# CUBO4X4X4.net
KiCad netlist of a schematic drawn in EAGLE
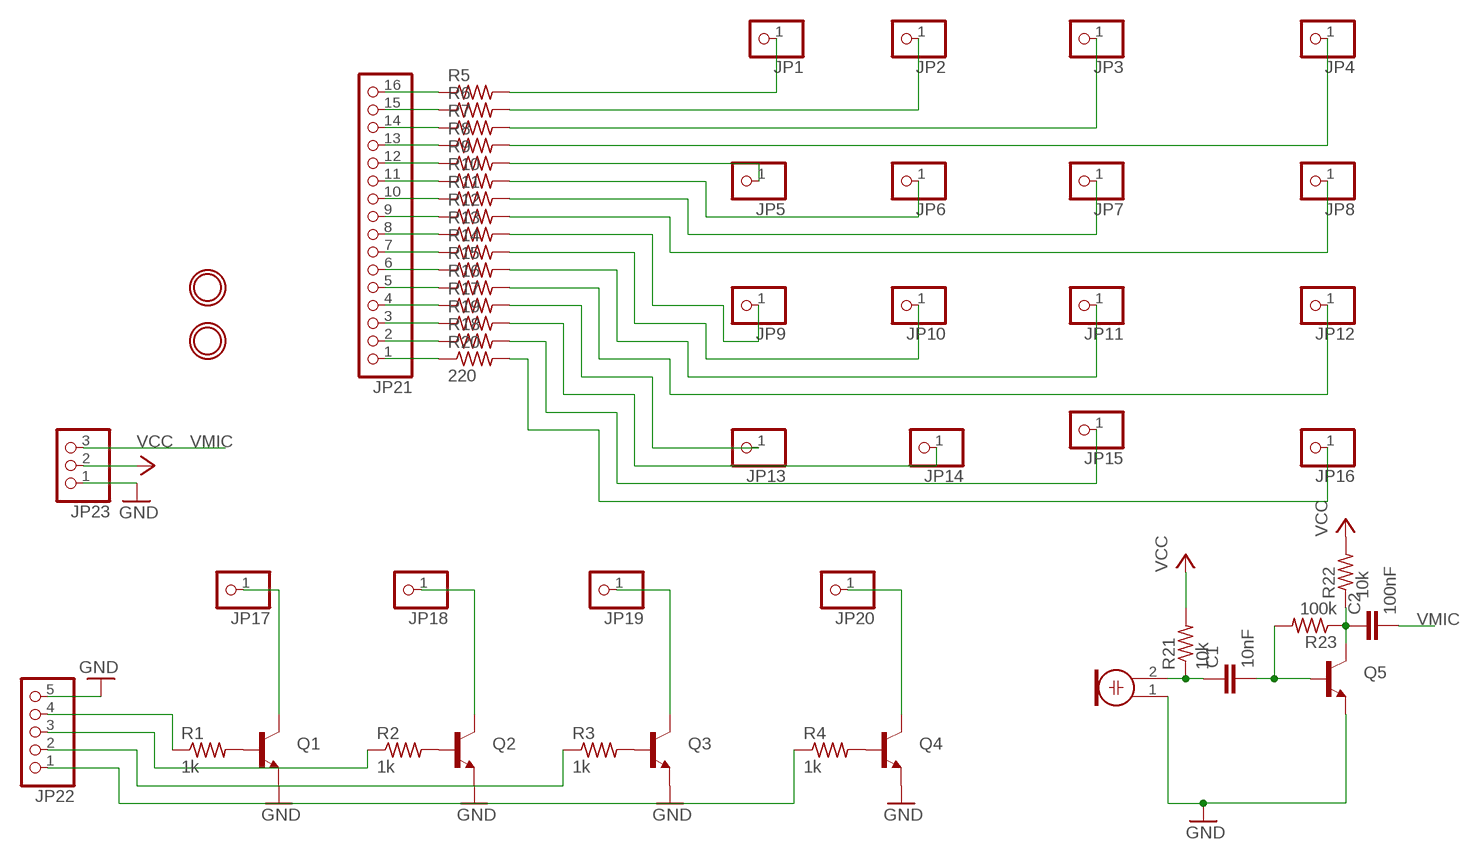
[diagram p0: schematic, sheet 1]

(export (version "E")
  (design (tool "Eeschema 10.0.6"))
  (components
    (comp (ref "C1")
      (value "10nF")
      (footprint "eagle-import:C2.5-2")
      (libsource (lib "eagle-import") (part "C2.5/2"))
    )
    (comp (ref "C2")
      (value "100nF")
      (footprint "eagle-import:C2.5-2")
      (libsource (lib "eagle-import") (part "C2.5/2"))
    )
    (comp (ref "JP1")
      (value "PINHD-1X1")
      (footprint "eagle-import:1X01")
      (libsource (lib "eagle-import") (part "PINHD-1X1"))
    )
    (comp (ref "JP2")
      (value "PINHD-1X1")
      (footprint "eagle-import:1X01")
      (libsource (lib "eagle-import") (part "PINHD-1X1"))
    )
    (comp (ref "JP3")
      (value "PINHD-1X1")
      (footprint "eagle-import:1X01")
      (libsource (lib "eagle-import") (part "PINHD-1X1"))
    )
    (comp (ref "JP4")
      (value "PINHD-1X1")
      (footprint "eagle-import:1X01")
      (libsource (lib "eagle-import") (part "PINHD-1X1"))
    )
    (comp (ref "JP5")
      (value "PINHD-1X1")
      (footprint "eagle-import:1X01")
      (libsource (lib "eagle-import") (part "PINHD-1X1"))
    )
    (comp (ref "JP6")
      (value "PINHD-1X1")
      (footprint "eagle-import:1X01")
      (libsource (lib "eagle-import") (part "PINHD-1X1"))
    )
    (comp (ref "JP7")
      (value "PINHD-1X1")
      (footprint "eagle-import:1X01")
      (libsource (lib "eagle-import") (part "PINHD-1X1"))
    )
    (comp (ref "JP8")
      (value "PINHD-1X1")
      (footprint "eagle-import:1X01")
      (libsource (lib "eagle-import") (part "PINHD-1X1"))
    )
    (comp (ref "JP9")
      (value "PINHD-1X1")
      (footprint "eagle-import:1X01")
      (libsource (lib "eagle-import") (part "PINHD-1X1"))
    )
    (comp (ref "JP10")
      (value "PINHD-1X1")
      (footprint "eagle-import:1X01")
      (libsource (lib "eagle-import") (part "PINHD-1X1"))
    )
    (comp (ref "JP11")
      (value "PINHD-1X1")
      (footprint "eagle-import:1X01")
      (libsource (lib "eagle-import") (part "PINHD-1X1"))
    )
    (comp (ref "JP12")
      (value "PINHD-1X1")
      (footprint "eagle-import:1X01")
      (libsource (lib "eagle-import") (part "PINHD-1X1"))
    )
    (comp (ref "JP13")
      (value "PINHD-1X1")
      (footprint "eagle-import:1X01")
      (libsource (lib "eagle-import") (part "PINHD-1X1"))
    )
    (comp (ref "JP14")
      (value "PINHD-1X1")
      (footprint "eagle-import:1X01")
      (libsource (lib "eagle-import") (part "PINHD-1X1"))
    )
    (comp (ref "JP15")
      (value "PINHD-1X1")
      (footprint "eagle-import:1X01")
      (libsource (lib "eagle-import") (part "PINHD-1X1"))
    )
    (comp (ref "JP16")
      (value "PINHD-1X1")
      (footprint "eagle-import:1X01")
      (libsource (lib "eagle-import") (part "PINHD-1X1"))
    )
    (comp (ref "JP17")
      (value "PINHD-1X1")
      (footprint "eagle-import:1X01")
      (libsource (lib "eagle-import") (part "PINHD-1X1"))
    )
    (comp (ref "JP18")
      (value "PINHD-1X1")
      (footprint "eagle-import:1X01")
      (libsource (lib "eagle-import") (part "PINHD-1X1"))
    )
    (comp (ref "JP19")
      (value "PINHD-1X1")
      (footprint "eagle-import:1X01")
      (libsource (lib "eagle-import") (part "PINHD-1X1"))
    )
    (comp (ref "JP20")
      (value "PINHD-1X1")
      (footprint "eagle-import:1X01")
      (libsource (lib "eagle-import") (part "PINHD-1X1"))
    )
    (comp (ref "JP21")
      (value "PINHD-1X16")
      (footprint "eagle-import:1X16")
      (libsource (lib "eagle-import") (part "PINHD-1X16"))
    )
    (comp (ref "JP22")
      (value "PINHD-1X5")
      (footprint "eagle-import:1X05")
      (libsource (lib "eagle-import") (part "PINHD-1X5"))
    )
    (comp (ref "JP23")
      (value "PINHD-1X3")
      (footprint "eagle-import:1X03")
      (libsource (lib "eagle-import") (part "PINHD-1X3"))
    )
    (comp (ref "M1")
      (value "ELECTRET_MICROPHON-WM.64PN")
      (footprint "eagle-import:WM-64PN")
      (libsource (lib "eagle-import") (part "ELECTRET_MICROPHON-WM.64PN"))
    )
    (comp (ref "Q1")
      (value "TRANSISTOR_NPNTO-92-AMMO")
      (footprint "eagle-import:TO-92-AMMO")
      (libsource (lib "eagle-import") (part "TRANSISTOR_NPNTO-92-AMMO"))
    )
    (comp (ref "Q2")
      (value "TRANSISTOR_NPNTO-92-AMMO")
      (footprint "eagle-import:TO-92-AMMO")
      (libsource (lib "eagle-import") (part "TRANSISTOR_NPNTO-92-AMMO"))
    )
    (comp (ref "Q3")
      (value "TRANSISTOR_NPNTO-92-AMMO")
      (footprint "eagle-import:TO-92-AMMO")
      (libsource (lib "eagle-import") (part "TRANSISTOR_NPNTO-92-AMMO"))
    )
    (comp (ref "Q4")
      (value "TRANSISTOR_NPNTO-92-AMMO")
      (footprint "eagle-import:TO-92-AMMO")
      (libsource (lib "eagle-import") (part "TRANSISTOR_NPNTO-92-AMMO"))
    )
    (comp (ref "Q5")
      (value "TRANSISTOR_NPNTO-92-AMMO")
      (footprint "eagle-import:TO-92-AMMO")
      (libsource (lib "eagle-import") (part "TRANSISTOR_NPNTO-92-AMMO"))
    )
    (comp (ref "R1")
      (value "1k")
      (footprint "eagle-import:0207_10")
      (libsource (lib "eagle-import") (part "R-US_0207/10"))
    )
    (comp (ref "R2")
      (value "1k")
      (footprint "eagle-import:0207_10")
      (libsource (lib "eagle-import") (part "R-US_0207/10"))
    )
    (comp (ref "R3")
      (value "1k")
      (footprint "eagle-import:0207_10")
      (libsource (lib "eagle-import") (part "R-US_0207/10"))
    )
    (comp (ref "R4")
      (value "1k")
      (footprint "eagle-import:0207_10")
      (libsource (lib "eagle-import") (part "R-US_0207/10"))
    )
    (comp (ref "R5")
      (value "R-US_0207/10")
      (footprint "eagle-import:0207_10")
      (libsource (lib "eagle-import") (part "R-US_0207/10"))
    )
    (comp (ref "R6")
      (value "R-US_0207/10")
      (footprint "eagle-import:0207_10")
      (libsource (lib "eagle-import") (part "R-US_0207/10"))
    )
    (comp (ref "R7")
      (value "R-US_0207/10")
      (footprint "eagle-import:0207_10")
      (libsource (lib "eagle-import") (part "R-US_0207/10"))
    )
    (comp (ref "R8")
      (value "R-US_0207/10")
      (footprint "eagle-import:0207_10")
      (libsource (lib "eagle-import") (part "R-US_0207/10"))
    )
    (comp (ref "R9")
      (value "R-US_0207/10")
      (footprint "eagle-import:0207_10")
      (libsource (lib "eagle-import") (part "R-US_0207/10"))
    )
    (comp (ref "R10")
      (value "R-US_0207/10")
      (footprint "eagle-import:0207_10")
      (libsource (lib "eagle-import") (part "R-US_0207/10"))
    )
    (comp (ref "R11")
      (value "R-US_0207/10")
      (footprint "eagle-import:0207_10")
      (libsource (lib "eagle-import") (part "R-US_0207/10"))
    )
    (comp (ref "R12")
      (value "R-US_0207/10")
      (footprint "eagle-import:0207_10")
      (libsource (lib "eagle-import") (part "R-US_0207/10"))
    )
    (comp (ref "R13")
      (value "R-US_0207/10")
      (footprint "eagle-import:0207_10")
      (libsource (lib "eagle-import") (part "R-US_0207/10"))
    )
    (comp (ref "R14")
      (value "R-US_0207/10")
      (footprint "eagle-import:0207_10")
      (libsource (lib "eagle-import") (part "R-US_0207/10"))
    )
    (comp (ref "R15")
      (value "R-US_0207/10")
      (footprint "eagle-import:0207_10")
      (libsource (lib "eagle-import") (part "R-US_0207/10"))
    )
    (comp (ref "R16")
      (value "R-US_0207/10")
      (footprint "eagle-import:0207_10")
      (libsource (lib "eagle-import") (part "R-US_0207/10"))
    )
    (comp (ref "R17")
      (value "R-US_0207/10")
      (footprint "eagle-import:0207_10")
      (libsource (lib "eagle-import") (part "R-US_0207/10"))
    )
    (comp (ref "R18")
      (value "R-US_0207/10")
      (footprint "eagle-import:0207_10")
      (libsource (lib "eagle-import") (part "R-US_0207/10"))
    )
    (comp (ref "R19")
      (value "R-US_0207/10")
      (footprint "eagle-import:0207_10")
      (libsource (lib "eagle-import") (part "R-US_0207/10"))
    )
    (comp (ref "R20")
      (value "220")
      (footprint "eagle-import:0207_10")
      (libsource (lib "eagle-import") (part "R-US_0207/10"))
    )
    (comp (ref "R21")
      (value "10k")
      (footprint "eagle-import:0207_10")
      (libsource (lib "eagle-import") (part "R-US_0207/10"))
    )
    (comp (ref "R22")
      (value "10k")
      (footprint "eagle-import:0207_10")
      (libsource (lib "eagle-import") (part "R-US_0207/10"))
    )
    (comp (ref "R23")
      (value "100k")
      (footprint "eagle-import:0207_10")
      (libsource (lib "eagle-import") (part "R-US_0207/10"))
    )
    (comp (ref "U$7")
      (value "MOUNTINGHOLE2.5_THICK")
      (footprint "eagle-import:MOUNTINGHOLE_2.5_PLATED_THICK")
      (libsource (lib "eagle-import") (part "MOUNTINGHOLE2.5_THICK"))
    )
    (comp (ref "U$8")
      (value "MOUNTINGHOLE2.5_THICK")
      (footprint "eagle-import:MOUNTINGHOLE_2.5_PLATED_THICK")
      (libsource (lib "eagle-import") (part "MOUNTINGHOLE2.5_THICK"))
    )
  )
  (nets
    (net (code "1") (name "/VMIC") (class "Default")
      (node (ref "C2") (pin "1") (pinfunction "1_1") (pintype "passive"))
      (node (ref "C2") (pin "2") (pinfunction "2_2") (pintype "passive"))
      (node (ref "JP23") (pin "3") (pinfunction "3_3") (pintype "passive"))
      (node (ref "Q5") (pin "3") (pinfunction "C_3") (pintype "passive"))
      (node (ref "R22") (pin "1") (pinfunction "1_1") (pintype "passive"))
      (node (ref "R23") (pin "1") (pinfunction "1_1") (pintype "passive"))
    )
    (net (code "2") (name "GND") (class "Default")
      (node (ref "JP22") (pin "5") (pinfunction "5_5") (pintype "passive"))
      (node (ref "JP23") (pin "1") (pinfunction "1_1") (pintype "passive"))
      (node (ref "M1") (pin "1") (pinfunction "1_1") (pintype "passive"))
      (node (ref "Q1") (pin "1") (pinfunction "E_1") (pintype "passive"))
      (node (ref "Q2") (pin "1") (pinfunction "E_1") (pintype "passive"))
      (node (ref "Q3") (pin "1") (pinfunction "E_1") (pintype "passive"))
      (node (ref "Q4") (pin "1") (pinfunction "E_1") (pintype "passive"))
      (node (ref "Q5") (pin "1") (pinfunction "E_1") (pintype "passive"))
    )
    (net (code "3") (name "Net-(C1-Pad1)") (class "Default")
      (node (ref "C1") (pin "1") (pinfunction "1_1") (pintype "passive"))
      (node (ref "M1") (pin "2") (pinfunction "2_2") (pintype "passive"))
      (node (ref "R21") (pin "1") (pinfunction "1_1") (pintype "passive"))
    )
    (net (code "4") (name "Net-(JP1-Pad1)") (class "Default")
      (node (ref "JP1") (pin "1") (pinfunction "1_1") (pintype "passive"))
      (node (ref "R5") (pin "2") (pinfunction "2_2") (pintype "passive"))
    )
    (net (code "5") (name "Net-(JP2-Pad1)") (class "Default")
      (node (ref "JP2") (pin "1") (pinfunction "1_1") (pintype "passive"))
      (node (ref "R6") (pin "2") (pinfunction "2_2") (pintype "passive"))
    )
    (net (code "6") (name "Net-(JP3-Pad1)") (class "Default")
      (node (ref "JP3") (pin "1") (pinfunction "1_1") (pintype "passive"))
      (node (ref "R7") (pin "2") (pinfunction "2_2") (pintype "passive"))
    )
    (net (code "7") (name "Net-(JP4-Pad1)") (class "Default")
      (node (ref "JP4") (pin "1") (pinfunction "1_1") (pintype "passive"))
      (node (ref "R8") (pin "2") (pinfunction "2_2") (pintype "passive"))
    )
    (net (code "8") (name "Net-(JP5-Pad1)") (class "Default")
      (node (ref "JP5") (pin "1") (pinfunction "1_1") (pintype "passive"))
      (node (ref "R9") (pin "2") (pinfunction "2_2") (pintype "passive"))
    )
    (net (code "9") (name "Net-(JP6-Pad1)") (class "Default")
      (node (ref "JP6") (pin "1") (pinfunction "1_1") (pintype "passive"))
      (node (ref "R10") (pin "2") (pinfunction "2_2") (pintype "passive"))
    )
    (net (code "10") (name "Net-(JP7-Pad1)") (class "Default")
      (node (ref "JP7") (pin "1") (pinfunction "1_1") (pintype "passive"))
      (node (ref "R11") (pin "2") (pinfunction "2_2") (pintype "passive"))
    )
    (net (code "11") (name "Net-(JP8-Pad1)") (class "Default")
      (node (ref "JP8") (pin "1") (pinfunction "1_1") (pintype "passive"))
      (node (ref "R12") (pin "2") (pinfunction "2_2") (pintype "passive"))
    )
    (net (code "12") (name "Net-(JP9-Pad1)") (class "Default")
      (node (ref "JP9") (pin "1") (pinfunction "1_1") (pintype "passive"))
      (node (ref "R13") (pin "2") (pinfunction "2_2") (pintype "passive"))
    )
    (net (code "13") (name "Net-(JP10-Pad1)") (class "Default")
      (node (ref "JP10") (pin "1") (pinfunction "1_1") (pintype "passive"))
      (node (ref "R14") (pin "2") (pinfunction "2_2") (pintype "passive"))
    )
    (net (code "14") (name "Net-(JP11-Pad1)") (class "Default")
      (node (ref "JP11") (pin "1") (pinfunction "1_1") (pintype "passive"))
      (node (ref "R15") (pin "2") (pinfunction "2_2") (pintype "passive"))
    )
    (net (code "15") (name "Net-(JP12-Pad1)") (class "Default")
      (node (ref "JP12") (pin "1") (pinfunction "1_1") (pintype "passive"))
      (node (ref "R16") (pin "2") (pinfunction "2_2") (pintype "passive"))
    )
    (net (code "16") (name "Net-(JP13-Pad1)") (class "Default")
      (node (ref "JP13") (pin "1") (pinfunction "1_1") (pintype "passive"))
      (node (ref "R17") (pin "2") (pinfunction "2_2") (pintype "passive"))
    )
    (net (code "17") (name "Net-(JP14-Pad1)") (class "Default")
      (node (ref "JP14") (pin "1") (pinfunction "1_1") (pintype "passive"))
      (node (ref "R19") (pin "2") (pinfunction "2_2") (pintype "passive"))
    )
    (net (code "18") (name "Net-(JP15-Pad1)") (class "Default")
      (node (ref "JP15") (pin "1") (pinfunction "1_1") (pintype "passive"))
      (node (ref "R18") (pin "2") (pinfunction "2_2") (pintype "passive"))
    )
    (net (code "19") (name "Net-(JP16-Pad1)") (class "Default")
      (node (ref "JP16") (pin "1") (pinfunction "1_1") (pintype "passive"))
      (node (ref "R20") (pin "2") (pinfunction "2_2") (pintype "passive"))
    )
    (net (code "20") (name "Net-(JP21-Pad1)") (class "Default")
      (node (ref "JP21") (pin "1") (pinfunction "1_1") (pintype "passive"))
      (node (ref "R20") (pin "1") (pinfunction "1_1") (pintype "passive"))
    )
    (net (code "21") (name "Net-(JP21-Pad2)") (class "Default")
      (node (ref "JP21") (pin "2") (pinfunction "2_2") (pintype "passive"))
      (node (ref "R18") (pin "1") (pinfunction "1_1") (pintype "passive"))
    )
    (net (code "22") (name "Net-(JP21-Pad3)") (class "Default")
      (node (ref "JP21") (pin "3") (pinfunction "3_3") (pintype "passive"))
      (node (ref "R19") (pin "1") (pinfunction "1_1") (pintype "passive"))
    )
    (net (code "23") (name "Net-(JP21-Pad4)") (class "Default")
      (node (ref "JP21") (pin "4") (pinfunction "4_4") (pintype "passive"))
      (node (ref "R17") (pin "1") (pinfunction "1_1") (pintype "passive"))
    )
    (net (code "24") (name "Net-(JP21-Pad5)") (class "Default")
      (node (ref "JP21") (pin "5") (pinfunction "5_5") (pintype "passive"))
      (node (ref "R16") (pin "1") (pinfunction "1_1") (pintype "passive"))
    )
    (net (code "25") (name "Net-(JP21-Pad6)") (class "Default")
      (node (ref "JP21") (pin "6") (pinfunction "6_6") (pintype "passive"))
      (node (ref "R15") (pin "1") (pinfunction "1_1") (pintype "passive"))
    )
    (net (code "26") (name "Net-(JP21-Pad7)") (class "Default")
      (node (ref "JP21") (pin "7") (pinfunction "7_7") (pintype "passive"))
      (node (ref "R14") (pin "1") (pinfunction "1_1") (pintype "passive"))
    )
    (net (code "27") (name "Net-(JP21-Pad8)") (class "Default")
      (node (ref "JP21") (pin "8") (pinfunction "8_8") (pintype "passive"))
      (node (ref "R13") (pin "1") (pinfunction "1_1") (pintype "passive"))
    )
    (net (code "28") (name "Net-(JP21-Pad9)") (class "Default")
      (node (ref "JP21") (pin "9") (pinfunction "9_9") (pintype "passive"))
      (node (ref "R12") (pin "1") (pinfunction "1_1") (pintype "passive"))
    )
    (net (code "29") (name "Net-(JP21-Pad10)") (class "Default")
      (node (ref "JP21") (pin "10") (pinfunction "10_10") (pintype "passive"))
      (node (ref "R11") (pin "1") (pinfunction "1_1") (pintype "passive"))
    )
    (net (code "30") (name "Net-(JP21-Pad11)") (class "Default")
      (node (ref "JP21") (pin "11") (pinfunction "11_11") (pintype "passive"))
      (node (ref "R10") (pin "1") (pinfunction "1_1") (pintype "passive"))
    )
    (net (code "31") (name "Net-(JP21-Pad12)") (class "Default")
      (node (ref "JP21") (pin "12") (pinfunction "12_12") (pintype "passive"))
      (node (ref "R9") (pin "1") (pinfunction "1_1") (pintype "passive"))
    )
    (net (code "32") (name "Net-(JP21-Pad13)") (class "Default")
      (node (ref "JP21") (pin "13") (pinfunction "13_13") (pintype "passive"))
      (node (ref "R8") (pin "1") (pinfunction "1_1") (pintype "passive"))
    )
    (net (code "33") (name "Net-(JP21-Pad14)") (class "Default")
      (node (ref "JP21") (pin "14") (pinfunction "14_14") (pintype "passive"))
      (node (ref "R7") (pin "1") (pinfunction "1_1") (pintype "passive"))
    )
    (net (code "34") (name "Net-(JP21-Pad15)") (class "Default")
      (node (ref "JP21") (pin "15") (pinfunction "15_15") (pintype "passive"))
      (node (ref "R6") (pin "1") (pinfunction "1_1") (pintype "passive"))
    )
    (net (code "35") (name "Net-(JP21-Pad16)") (class "Default")
      (node (ref "JP21") (pin "16") (pinfunction "16_16") (pintype "passive"))
      (node (ref "R5") (pin "1") (pinfunction "1_1") (pintype "passive"))
    )
    (net (code "36") (name "Net-(JP22-Pad1)") (class "Default")
      (node (ref "JP22") (pin "1") (pinfunction "1_1") (pintype "passive"))
      (node (ref "R4") (pin "1") (pinfunction "1_1") (pintype "passive"))
    )
    (net (code "37") (name "Net-(JP22-Pad2)") (class "Default")
      (node (ref "JP22") (pin "2") (pinfunction "2_2") (pintype "passive"))
      (node (ref "R3") (pin "1") (pinfunction "1_1") (pintype "passive"))
    )
    (net (code "38") (name "Net-(JP22-Pad3)") (class "Default")
      (node (ref "JP22") (pin "3") (pinfunction "3_3") (pintype "passive"))
      (node (ref "R2") (pin "1") (pinfunction "1_1") (pintype "passive"))
    )
    (net (code "39") (name "Net-(JP22-Pad4)") (class "Default")
      (node (ref "JP22") (pin "4") (pinfunction "4_4") (pintype "passive"))
      (node (ref "R1") (pin "1") (pinfunction "1_1") (pintype "passive"))
    )
    (net (code "40") (name "Net-(Q1-B)") (class "Default")
      (node (ref "Q1") (pin "2") (pinfunction "B_2") (pintype "passive"))
      (node (ref "R1") (pin "2") (pinfunction "2_2") (pintype "passive"))
    )
    (net (code "41") (name "Net-(Q1-C)") (class "Default")
      (node (ref "JP17") (pin "1") (pinfunction "1_1") (pintype "passive"))
      (node (ref "Q1") (pin "3") (pinfunction "C_3") (pintype "passive"))
    )
    (net (code "42") (name "Net-(Q2-B)") (class "Default")
      (node (ref "Q2") (pin "2") (pinfunction "B_2") (pintype "passive"))
      (node (ref "R2") (pin "2") (pinfunction "2_2") (pintype "passive"))
    )
    (net (code "43") (name "Net-(Q2-C)") (class "Default")
      (node (ref "JP18") (pin "1") (pinfunction "1_1") (pintype "passive"))
      (node (ref "Q2") (pin "3") (pinfunction "C_3") (pintype "passive"))
    )
    (net (code "44") (name "Net-(Q3-B)") (class "Default")
      (node (ref "Q3") (pin "2") (pinfunction "B_2") (pintype "passive"))
      (node (ref "R3") (pin "2") (pinfunction "2_2") (pintype "passive"))
    )
    (net (code "45") (name "Net-(Q3-C)") (class "Default")
      (node (ref "JP19") (pin "1") (pinfunction "1_1") (pintype "passive"))
      (node (ref "Q3") (pin "3") (pinfunction "C_3") (pintype "passive"))
    )
    (net (code "46") (name "Net-(Q4-B)") (class "Default")
      (node (ref "Q4") (pin "2") (pinfunction "B_2") (pintype "passive"))
      (node (ref "R4") (pin "2") (pinfunction "2_2") (pintype "passive"))
    )
    (net (code "47") (name "Net-(Q4-C)") (class "Default")
      (node (ref "JP20") (pin "1") (pinfunction "1_1") (pintype "passive"))
      (node (ref "Q4") (pin "3") (pinfunction "C_3") (pintype "passive"))
    )
    (net (code "48") (name "Net-(Q5-B)") (class "Default")
      (node (ref "C1") (pin "2") (pinfunction "2_2") (pintype "passive"))
      (node (ref "Q5") (pin "2") (pinfunction "B_2") (pintype "passive"))
      (node (ref "R23") (pin "2") (pinfunction "2_2") (pintype "passive"))
    )
    (net (code "49") (name "VCC") (class "Default")
      (node (ref "JP23") (pin "2") (pinfunction "2_2") (pintype "passive"))
      (node (ref "R21") (pin "2") (pinfunction "2_2") (pintype "passive"))
      (node (ref "R22") (pin "2") (pinfunction "2_2") (pintype "passive"))
    )
  )
)
